# Kandidat.net
KiCad netlist of a schematic drawn in Altium Designer
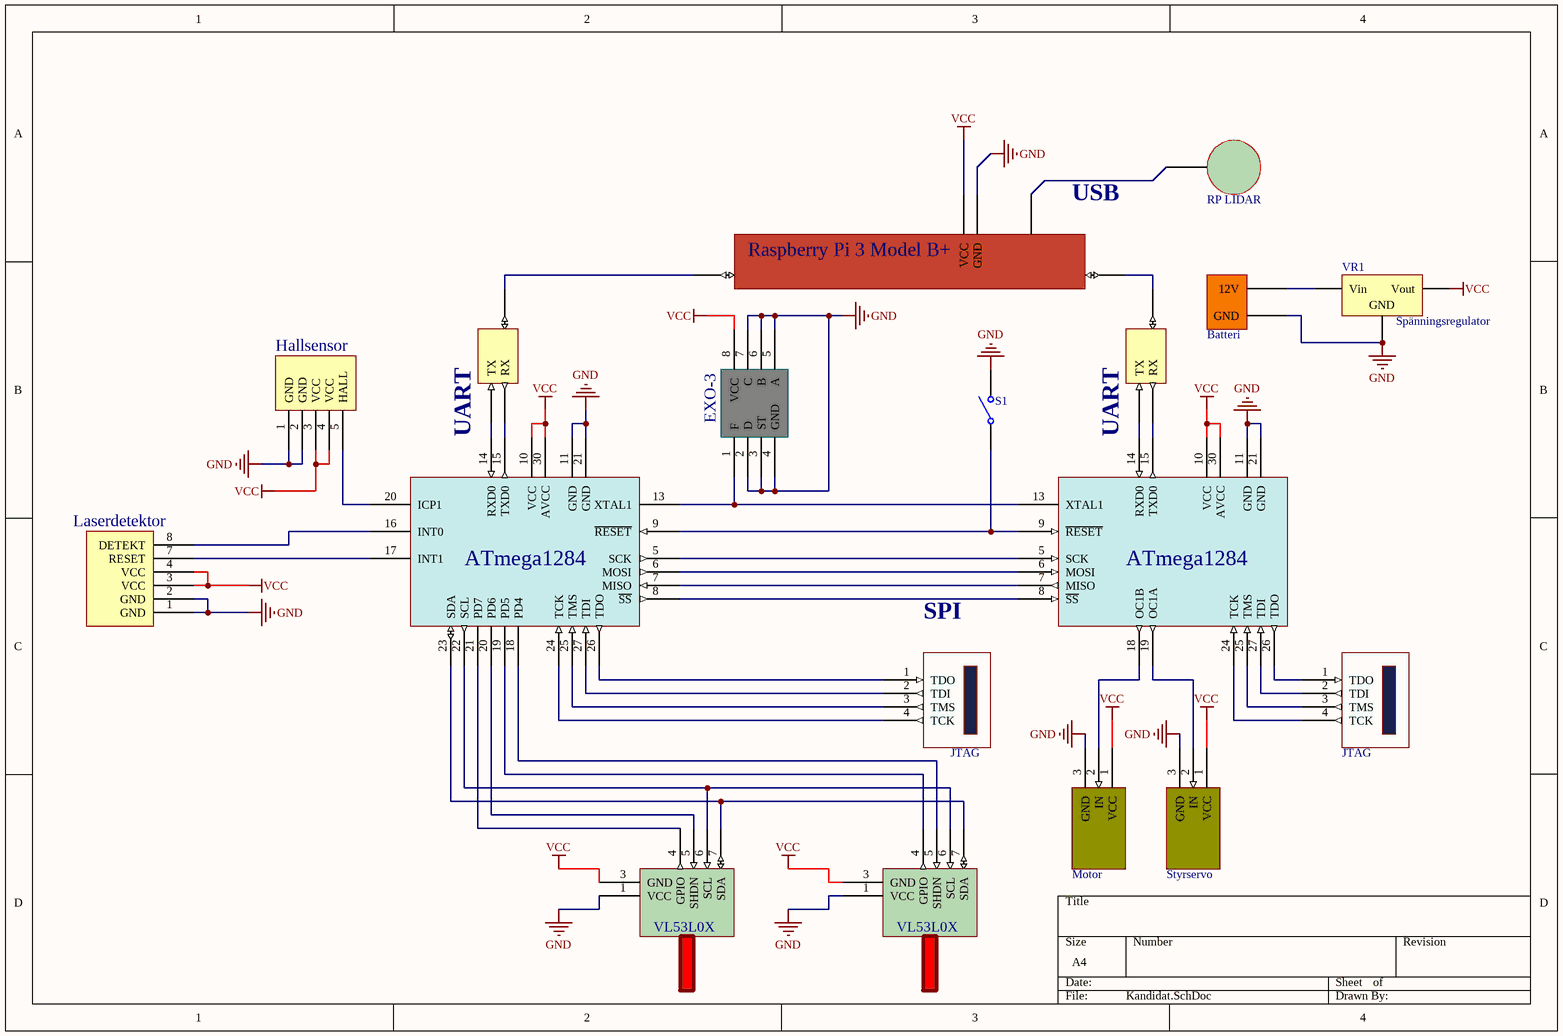
[diagram p0: Kandidat.SchDoc]

(export (version "E")
  (design (tool "Eeschema 10.0.6"))
  (components
    (comp (ref "3") (value "JTAG") (libsource (lib "bOYSEN") (part "JTAG")))
    (comp (ref "4") (value "JTAG") (libsource (lib "bOYSEN") (part "JTAG")))
    (comp (ref "14") (value "Styrservo") (libsource (lib "bOYSEN") (part "Styrservo")))
    (comp (ref "15") (value "Motor") (libsource (lib "bOYSEN") (part "Motor")))
    (comp (ref "21") (value "RP LIDAR") (libsource (lib "bOYSEN") (part "RP LIDAR")))
    (comp (ref "23") (value "Batteri") (libsource (lib "bOYSEN") (part "Batteri")))
    (comp (ref "56") (value "VL53L0X") (libsource (lib "bOYSEN") (part "VL53L0X")))
    (comp (ref "76") (value "VL53L0X") (libsource (lib "bOYSEN") (part "VL53L0X")))
    (comp (ref "123") (value "usb->uart") (libsource (lib "bOYSEN") (part "usb-{gt}uart")))
    (comp (ref "312") (value "usb->uart") (libsource (lib "bOYSEN") (part "usb-{gt}uart")))
    (comp (ref "657") (value "EXO-3") (libsource (lib "bOYSEN") (part "EXO-3")))
    (comp (ref "1233")
      (value "Raspberry Pi 3 Model B+")
      (libsource (lib "bOYSEN") (part "Raspberry Pi 3 Model B+"))
    )
    (comp (ref "2345") (value "Laserdetektor") (libsource (lib "bOYSEN") (part "Laserdetektor")))
    (comp (ref "3475") (value "Hallsensor") (libsource (lib "bOYSEN") (part "Hallsensor")))
    (comp (ref "44235") (value "ATmega1284") (libsource (lib "bOYSEN") (part "ATmega1284styr")))
    (comp (ref "56324") (value "ATmega1284") (libsource (lib "bOYSEN") (part "ATmega1284Sens")))
    (comp (ref "S1")
      (value "SW-SPST")
      (footprint "SPST-2")
      (description "Single-Pole, Single-Throw Switch")
      (fields (field (name "PUBLISHER") "Altium Limited"))
      (libsource (lib "Miscellaneous Devices") (part "SW-SPST"))
    )
    (comp (ref "VR1")
      (value "Spänningsregulator")
      (footprint "D2PAK_N")
      (description "Voltage Regulator")
      (fields (field (name "PUBLISHER") "Altium Limited"))
      (libsource (lib "Miscellaneous Devices") (part "Volt Reg"))
    )
  )
  (nets
    (net (code "1") (name "GND") (class "Default")
      (node (ref "1233") (pin "40") (pinfunction "GND_40") (pintype "power_in"))
      (node (ref "14") (pin "3") (pinfunction "GND_3") (pintype "passive"))
      (node (ref "15") (pin "3") (pinfunction "GND_3") (pintype "passive"))
      (node (ref "23") (pin "55") (pinfunction "GND_55") (pintype "power_in"))
      (node (ref "2345") (pin "1") (pinfunction "GND_1") (pintype "passive"))
      (node (ref "2345") (pin "2") (pinfunction "GND_2") (pintype "passive"))
      (node (ref "3475") (pin "1") (pinfunction "GND_1") (pintype "passive"))
      (node (ref "3475") (pin "2") (pinfunction "GND_2") (pintype "passive"))
      (node (ref "44235") (pin "11") (pinfunction "GND_11") (pintype "power_in"))
      (node (ref "44235") (pin "21") (pinfunction "GND_21") (pintype "power_in"))
      (node (ref "56") (pin "1") (pinfunction "VCC_1") (pintype "power_in"))
      (node (ref "56324") (pin "11") (pinfunction "GND_11") (pintype "power_in"))
      (node (ref "56324") (pin "21") (pinfunction "GND_21") (pintype "power_in"))
      (node (ref "657") (pin "2") (pinfunction "D_2") (pintype "passive"))
      (node (ref "657") (pin "3") (pinfunction "ST_3") (pintype "passive"))
      (node (ref "657") (pin "4") (pinfunction "GND_4") (pintype "passive"))
      (node (ref "657") (pin "5") (pinfunction "A_5") (pintype "passive"))
      (node (ref "657") (pin "6") (pinfunction "B_6") (pintype "passive"))
      (node (ref "657") (pin "7") (pinfunction "C_7") (pintype "passive"))
      (node (ref "76") (pin "1") (pinfunction "VCC_1") (pintype "power_in"))
      (node (ref "S1") (pin "2") (pinfunction "NO_2") (pintype "passive"))
      (node (ref "VR1") (pin "2") (pinfunction "GND_2") (pintype "passive"))
    )
    (net (code "2") (name "Net-(3-TCK)") (class "Default")
      (node (ref "3") (pin "4") (pinfunction "TCK_4") (pintype "output"))
      (node (ref "56324") (pin "24") (pinfunction "TCK_24") (pintype "input"))
    )
    (net (code "3") (name "Net-(3-TDI)") (class "Default")
      (node (ref "3") (pin "2") (pinfunction "TDI_2") (pintype "output"))
      (node (ref "56324") (pin "27") (pinfunction "TDI_27") (pintype "input"))
    )
    (net (code "4") (name "Net-(3-TDO)") (class "Default")
      (node (ref "3") (pin "1") (pinfunction "TDO_1") (pintype "input"))
      (node (ref "56324") (pin "26") (pinfunction "TDO_26") (pintype "output"))
    )
    (net (code "5") (name "Net-(3-TMS)") (class "Default")
      (node (ref "3") (pin "3") (pinfunction "TMS_3") (pintype "output"))
      (node (ref "56324") (pin "25") (pinfunction "TMS_25") (pintype "input"))
    )
    (net (code "6") (name "Net-(4-TCK)") (class "Default")
      (node (ref "4") (pin "4") (pinfunction "TCK_4") (pintype "output"))
      (node (ref "44235") (pin "24") (pinfunction "TCK_24") (pintype "input"))
    )
    (net (code "7") (name "Net-(4-TDI)") (class "Default")
      (node (ref "4") (pin "2") (pinfunction "TDI_2") (pintype "output"))
      (node (ref "44235") (pin "27") (pinfunction "TDI_27") (pintype "input"))
    )
    (net (code "8") (name "Net-(4-TDO)") (class "Default")
      (node (ref "4") (pin "1") (pinfunction "TDO_1") (pintype "input"))
      (node (ref "44235") (pin "26") (pinfunction "TDO_26") (pintype "output"))
    )
    (net (code "9") (name "Net-(4-TMS)") (class "Default")
      (node (ref "4") (pin "3") (pinfunction "TMS_3") (pintype "output"))
      (node (ref "44235") (pin "25") (pinfunction "TMS_25") (pintype "input"))
    )
    (net (code "10") (name "Net-(14-IN)") (class "Default")
      (node (ref "14") (pin "2") (pinfunction "IN_2") (pintype "input"))
      (node (ref "44235") (pin "19") (pinfunction "OC1A_19") (pintype "output"))
    )
    (net (code "11") (name "Net-(15-IN)") (class "Default")
      (node (ref "15") (pin "2") (pinfunction "IN_2") (pintype "input"))
      (node (ref "44235") (pin "18") (pinfunction "OC1B_18") (pintype "output"))
    )
    (net (code "12") (name "Net-(23-12V)") (class "Default")
      (node (ref "23") (pin "54") (pinfunction "12V_54") (pintype "power_in"))
      (node (ref "VR1") (pin "1") (pinfunction "Vin_1") (pintype "passive"))
    )
    (net (code "13") (name "Net-(56-GPIO)") (class "Default")
      (node (ref "56") (pin "4") (pinfunction "GPIO_4") (pintype "output"))
      (node (ref "56324") (pin "21") (pinfunction "PD7_21") (pintype "passive"))
    )
    (net (code "14") (name "Net-(56-SCL)") (class "Default")
      (node (ref "56") (pin "6") (pinfunction "SCL_6") (pintype "input"))
      (node (ref "56324") (pin "22") (pinfunction "SCL_22") (pintype "output"))
      (node (ref "76") (pin "6") (pinfunction "SCL_6") (pintype "input"))
    )
    (net (code "15") (name "Net-(56-SDA)") (class "Default")
      (node (ref "56") (pin "7") (pinfunction "SDA_7") (pintype "bidirectional"))
      (node (ref "56324") (pin "23") (pinfunction "SDA_23") (pintype "bidirectional"))
      (node (ref "76") (pin "7") (pinfunction "SDA_7") (pintype "bidirectional"))
    )
    (net (code "16") (name "Net-(56-SHDN)") (class "Default")
      (node (ref "56") (pin "5") (pinfunction "SHDN_5") (pintype "input"))
      (node (ref "56324") (pin "20") (pinfunction "PD6_20") (pintype "passive"))
    )
    (net (code "17") (name "Net-(123-RX)") (class "Default")
      (node (ref "123") (pin "42") (pinfunction "RX_42") (pintype "output"))
      (node (ref "44235") (pin "15") (pinfunction "TXD0_15") (pintype "output"))
    )
    (net (code "18") (name "Net-(123-TX)") (class "Default")
      (node (ref "123") (pin "43") (pinfunction "TX_43") (pintype "input"))
      (node (ref "44235") (pin "14") (pinfunction "RXD0_14") (pintype "input"))
    )
    (net (code "19") (name "Net-(312-RX)") (class "Default")
      (node (ref "312") (pin "42") (pinfunction "RX_42") (pintype "output"))
      (node (ref "56324") (pin "15") (pinfunction "TXD0_15") (pintype "output"))
    )
    (net (code "20") (name "Net-(312-TX)") (class "Default")
      (node (ref "312") (pin "43") (pinfunction "TX_43") (pintype "input"))
      (node (ref "56324") (pin "14") (pinfunction "RXD0_14") (pintype "input"))
    )
    (net (code "21") (name "Net-(1233-TX1)") (class "Default")
      (node (ref "1233") (pin "34") (pinfunction "TX1_34") (pintype "bidirectional"))
      (node (ref "312") (pin "44") (pinfunction "44_44") (pintype "bidirectional"))
    )
    (net (code "22") (name "Net-(1233-TX2)") (class "Default")
      (node (ref "123") (pin "44") (pinfunction "44_44") (pintype "bidirectional"))
      (node (ref "1233") (pin "35") (pinfunction "TX2_35") (pintype "bidirectional"))
    )
    (net (code "23") (name "Net-(2345-DETEKT)") (class "Default")
      (node (ref "2345") (pin "8") (pinfunction "DETEKT_8") (pintype "passive"))
      (node (ref "56324") (pin "16") (pinfunction "INT0_16") (pintype "passive"))
    )
    (net (code "24") (name "Net-(2345-RESET)") (class "Default")
      (node (ref "2345") (pin "7") (pinfunction "RESET_7") (pintype "passive"))
      (node (ref "56324") (pin "17") (pinfunction "INT1_17") (pintype "passive"))
    )
    (net (code "25") (name "Net-(3475-HALL)") (class "Default")
      (node (ref "3475") (pin "5") (pinfunction "HALL_5") (pintype "passive"))
      (node (ref "56324") (pin "20") (pinfunction "ICP1_20") (pintype "passive"))
    )
    (net (code "26") (name "Net-(44235-MISO)") (class "Default")
      (node (ref "44235") (pin "7") (pinfunction "MISO_7") (pintype "output"))
      (node (ref "56324") (pin "7") (pinfunction "MISO_7") (pintype "input"))
    )
    (net (code "27") (name "Net-(44235-MOSI)") (class "Default")
      (node (ref "44235") (pin "6") (pinfunction "MOSI_6") (pintype "input"))
      (node (ref "56324") (pin "6") (pinfunction "MOSI_6") (pintype "output"))
    )
    (net (code "28") (name "Net-(44235-SCK)") (class "Default")
      (node (ref "44235") (pin "5") (pinfunction "SCK_5") (pintype "input"))
      (node (ref "56324") (pin "5") (pinfunction "SCK_5") (pintype "output"))
    )
    (net (code "29") (name "Net-(44235-XTAL1)") (class "Default")
      (node (ref "44235") (pin "13") (pinfunction "XTAL1_13") (pintype "passive"))
      (node (ref "56324") (pin "13") (pinfunction "XTAL1_13") (pintype "passive"))
      (node (ref "657") (pin "1") (pinfunction "F_1") (pintype "passive"))
    )
    (net (code "30") (name "Net-(44235-~{RESET})") (class "Default")
      (node (ref "44235") (pin "9") (pinfunction "~{RESET}_9") (pintype "input"))
      (node (ref "56324") (pin "9") (pinfunction "~{RESET}_9") (pintype "input"))
      (node (ref "S1") (pin "1") (pinfunction "COMMON_1") (pintype "passive"))
    )
    (net (code "31") (name "Net-(44235-~{SS})") (class "Default")
      (node (ref "44235") (pin "8") (pinfunction "~{SS}_8") (pintype "input"))
      (node (ref "56324") (pin "8") (pinfunction "~{SS}_8") (pintype "output"))
    )
    (net (code "32") (name "Net-(56324-PD4)") (class "Default")
      (node (ref "56324") (pin "18") (pinfunction "PD4_18") (pintype "passive"))
      (node (ref "76") (pin "5") (pinfunction "SHDN_5") (pintype "input"))
    )
    (net (code "33") (name "Net-(56324-PD5)") (class "Default")
      (node (ref "56324") (pin "19") (pinfunction "PD5_19") (pintype "passive"))
      (node (ref "76") (pin "4") (pinfunction "GPIO_4") (pintype "output"))
    )
    (net (code "34") (name "VCC") (class "Default")
      (node (ref "1233") (pin "39") (pinfunction "VCC_39") (pintype "power_in"))
      (node (ref "14") (pin "1") (pinfunction "VCC_1") (pintype "passive"))
      (node (ref "15") (pin "1") (pinfunction "VCC_1") (pintype "passive"))
      (node (ref "2345") (pin "3") (pinfunction "VCC_3") (pintype "passive"))
      (node (ref "2345") (pin "4") (pinfunction "VCC_4") (pintype "passive"))
      (node (ref "3475") (pin "3") (pinfunction "VCC_3") (pintype "passive"))
      (node (ref "3475") (pin "4") (pinfunction "VCC_4") (pintype "passive"))
      (node (ref "44235") (pin "10") (pinfunction "VCC_10") (pintype "power_in"))
      (node (ref "44235") (pin "30") (pinfunction "AVCC_30") (pintype "power_in"))
      (node (ref "56") (pin "3") (pinfunction "GND_3") (pintype "power_in"))
      (node (ref "56324") (pin "10") (pinfunction "VCC_10") (pintype "power_in"))
      (node (ref "56324") (pin "30") (pinfunction "AVCC_30") (pintype "power_in"))
      (node (ref "657") (pin "8") (pinfunction "VCC_8") (pintype "passive"))
      (node (ref "76") (pin "3") (pinfunction "GND_3") (pintype "power_in"))
      (node (ref "VR1") (pin "3") (pinfunction "Vout_3") (pintype "passive"))
    )
    (net (code "35") (name "unconnected-(21-Pad39)") (class "Default")
      (node (ref "21") (pin "39") (pinfunction "39_39") (pintype "passive"))
    )
    (net (code "36") (name "unconnected-(1233-Pad38)") (class "Default")
      (node (ref "1233") (pin "38") (pinfunction "38_38") (pintype "passive"))
    )
  )
)
